# Grove-EMG_Sensor_v1_0.net
KiCad netlist of a schematic drawn in EAGLE
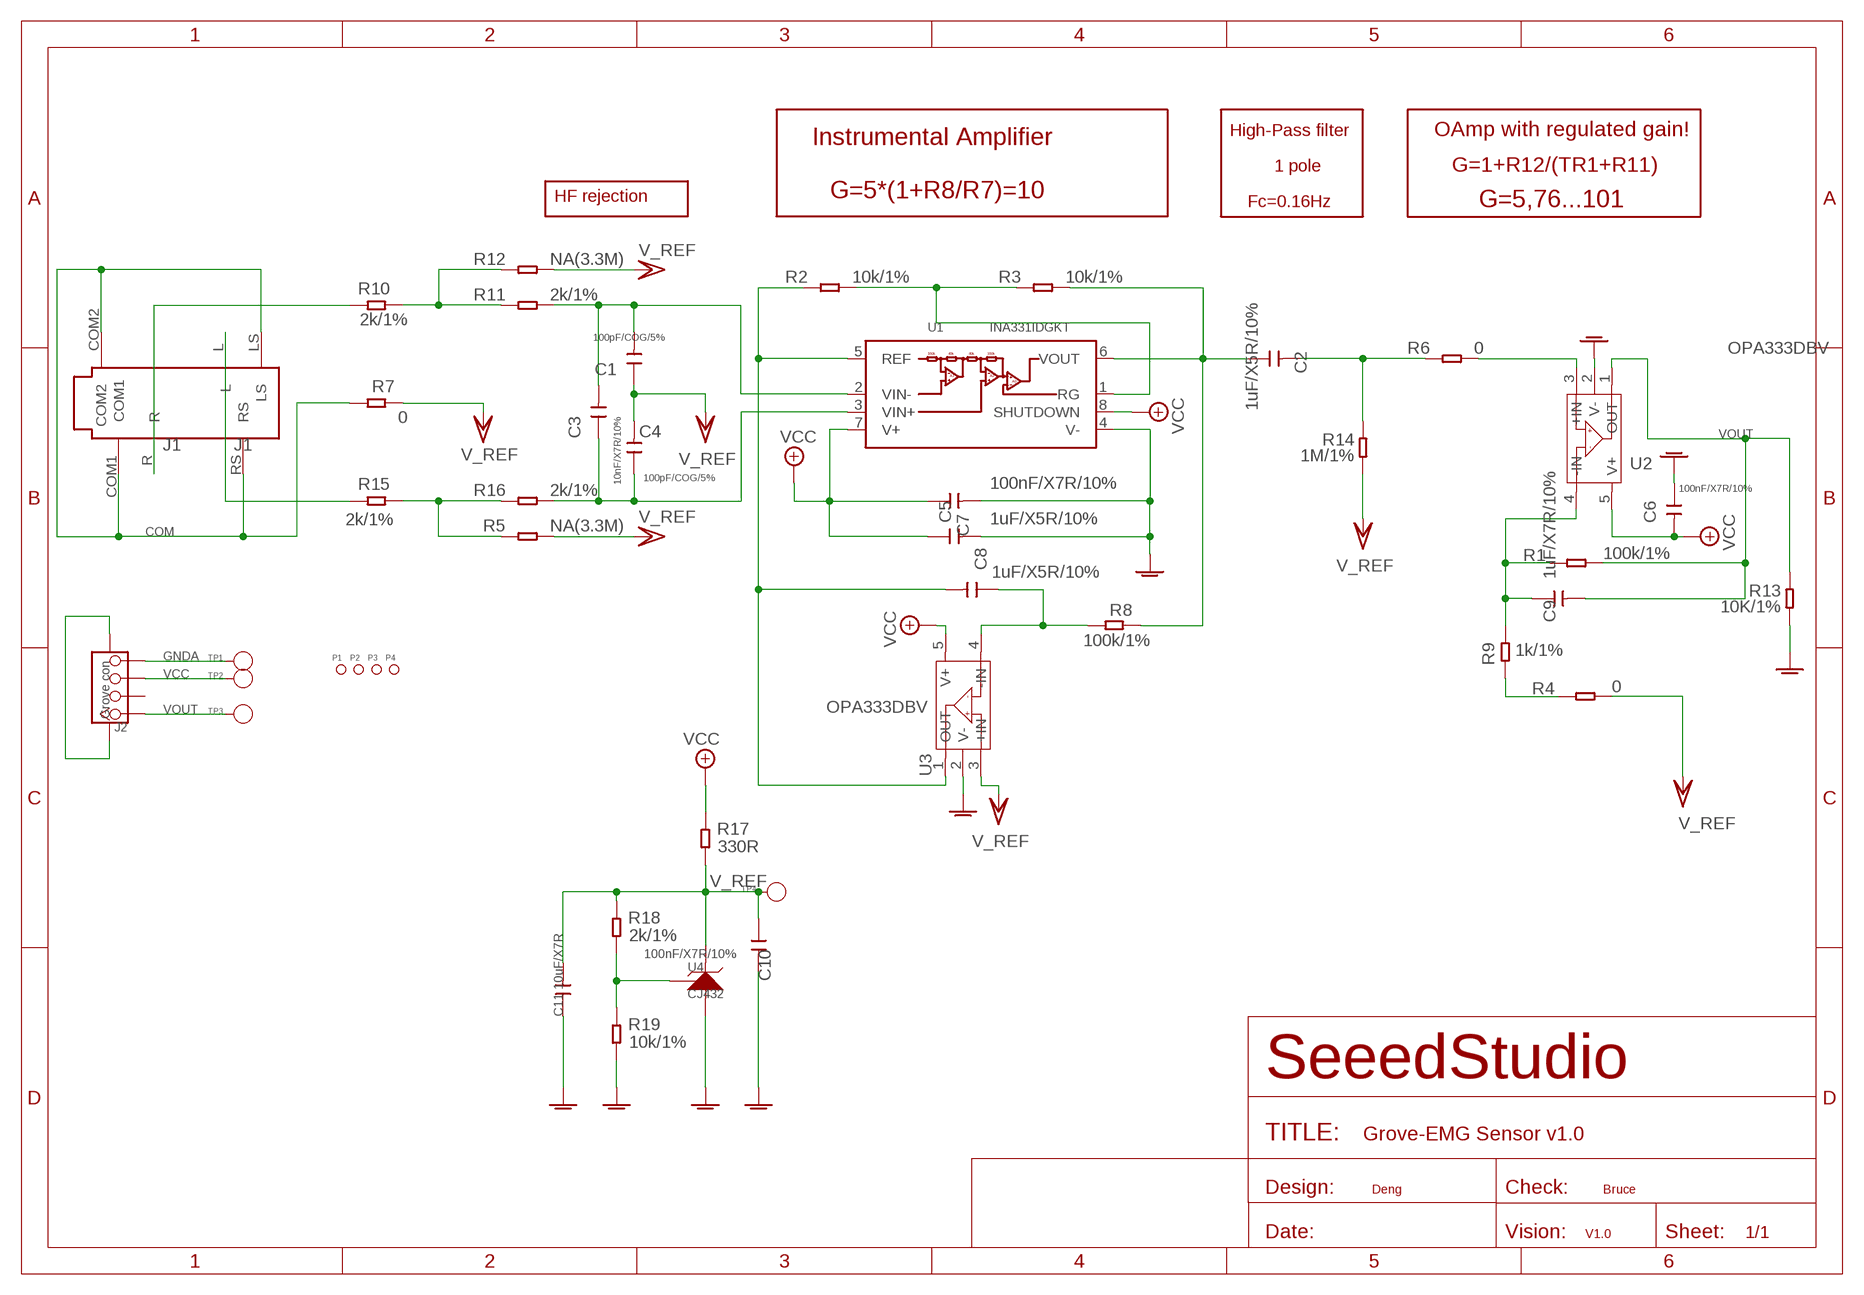
[diagram p0: schematic, sheet 1]

(export (version "E")
  (design (tool "Eeschema 10.0.6"))
  (components
    (comp (ref "C1")
      (value "100pF/COG/5%")
      (footprint "eagle-import:C0603")
      (libsource (lib "eagle-import") (part "C-0603"))
    )
    (comp (ref "C2")
      (value "1uF/X5R/10%")
      (footprint "eagle-import:C0603")
      (libsource (lib "eagle-import") (part "C-0603"))
    )
    (comp (ref "C3")
      (value "10nF/X7R/10%")
      (footprint "eagle-import:C0603")
      (libsource (lib "eagle-import") (part "C-0603"))
    )
    (comp (ref "C4")
      (value "100pF/COG/5%")
      (footprint "eagle-import:C0603")
      (libsource (lib "eagle-import") (part "C-0603"))
    )
    (comp (ref "C5")
      (value "100nF/X7R/10%")
      (footprint "eagle-import:C0603")
      (libsource (lib "eagle-import") (part "C-0603"))
    )
    (comp (ref "C6")
      (value "100nF/X7R/10%")
      (footprint "eagle-import:C0603")
      (libsource (lib "eagle-import") (part "C-0603"))
    )
    (comp (ref "C7")
      (value "1uF/X5R/10%")
      (footprint "eagle-import:C0603")
      (libsource (lib "eagle-import") (part "C-0603"))
    )
    (comp (ref "C8")
      (value "1uF/X5R/10%")
      (footprint "eagle-import:C0603")
      (libsource (lib "eagle-import") (part "C-0603"))
    )
    (comp (ref "C9")
      (value "1uF/X7R/10%")
      (footprint "eagle-import:C0603")
      (libsource (lib "eagle-import") (part "C-0603"))
    )
    (comp (ref "C10")
      (value "100nF/X7R/10%")
      (footprint "eagle-import:C0603")
      (libsource (lib "eagle-import") (part "C-0603"))
    )
    (comp (ref "C11")
      (value "10uF/X7R")
      (footprint "eagle-import:C0805")
      (libsource (lib "eagle-import") (part "C-0805"))
    )
    (comp (ref "J1")
      (value "J1")
      (footprint "eagle-import:6P-SMD-3.5-NEW")
      (libsource (lib "eagle-import") (part "AUDIO-6P-SMD"))
    )
    (comp (ref "J2")
      (value "Grove con")
      (footprint "eagle-import:4P-SMD-2.0")
      (libsource (lib "eagle-import") (part "TWIG-4P-2.0-SMD-FEMALE-REINFORCE'DD'"))
    )
    (comp (ref "P1")
      (value "PAD-MARK")
      (footprint "eagle-import:ROUND-MARK-1.0")
      (fields (field (name "PARTNO") "DNP"))
      (libsource (lib "eagle-import") (part "PAD-MARK"))
    )
    (comp (ref "P2")
      (value "PAD-MARK")
      (footprint "eagle-import:ROUND-MARK-1.0")
      (fields (field (name "PARTNO") "DNP"))
      (libsource (lib "eagle-import") (part "PAD-MARK"))
    )
    (comp (ref "P3")
      (value "PAD-MARK")
      (footprint "eagle-import:ROUND-MARK-1.0")
      (fields (field (name "PARTNO") "DNP"))
      (libsource (lib "eagle-import") (part "PAD-MARK"))
    )
    (comp (ref "P4")
      (value "PAD-MARK")
      (footprint "eagle-import:ROUND-MARK-1.0")
      (fields (field (name "PARTNO") "DNP"))
      (libsource (lib "eagle-import") (part "PAD-MARK"))
    )
    (comp (ref "R1")
      (value "100k/1%")
      (footprint "eagle-import:R0603")
      (libsource (lib "eagle-import") (part "R-0603"))
    )
    (comp (ref "R2")
      (value "10k/1%")
      (footprint "eagle-import:R0603")
      (libsource (lib "eagle-import") (part "R-0603"))
    )
    (comp (ref "R3")
      (value "10k/1%")
      (footprint "eagle-import:R0603")
      (libsource (lib "eagle-import") (part "R-0603"))
    )
    (comp (ref "R4")
      (value "0")
      (footprint "eagle-import:R0603")
      (libsource (lib "eagle-import") (part "R-0603"))
    )
    (comp (ref "R5")
      (value "NA(3.3M)")
      (footprint "eagle-import:R0603")
      (libsource (lib "eagle-import") (part "R-0603"))
    )
    (comp (ref "R6")
      (value "0")
      (footprint "eagle-import:R0603")
      (libsource (lib "eagle-import") (part "R-0603"))
    )
    (comp (ref "R7")
      (value "0")
      (footprint "eagle-import:R0603")
      (libsource (lib "eagle-import") (part "R-0603"))
    )
    (comp (ref "R8")
      (value "100k/1%")
      (footprint "eagle-import:R0603")
      (libsource (lib "eagle-import") (part "R-0603"))
    )
    (comp (ref "R9")
      (value "1k/1%")
      (footprint "eagle-import:R0603")
      (libsource (lib "eagle-import") (part "R-0603"))
    )
    (comp (ref "R10")
      (value "2k/1%")
      (footprint "eagle-import:R0603")
      (libsource (lib "eagle-import") (part "R-0603"))
    )
    (comp (ref "R11")
      (value "2k/1%")
      (footprint "eagle-import:R0603")
      (libsource (lib "eagle-import") (part "R-0603"))
    )
    (comp (ref "R12")
      (value "NA(3.3M)")
      (footprint "eagle-import:R0603")
      (libsource (lib "eagle-import") (part "R-0603"))
    )
    (comp (ref "R13")
      (value "10K/1%")
      (footprint "eagle-import:R0603")
      (libsource (lib "eagle-import") (part "R-0603"))
    )
    (comp (ref "R14")
      (value "1M/1%")
      (footprint "eagle-import:R0603")
      (libsource (lib "eagle-import") (part "R-0603"))
    )
    (comp (ref "R15")
      (value "2k/1%")
      (footprint "eagle-import:R0603")
      (libsource (lib "eagle-import") (part "R-0603"))
    )
    (comp (ref "R16")
      (value "2k/1%")
      (footprint "eagle-import:R0603")
      (libsource (lib "eagle-import") (part "R-0603"))
    )
    (comp (ref "R17")
      (value "330R")
      (footprint "eagle-import:R0603")
      (libsource (lib "eagle-import") (part "R-0603"))
    )
    (comp (ref "R18")
      (value "2k/1%")
      (footprint "eagle-import:R0603")
      (libsource (lib "eagle-import") (part "R-0603"))
    )
    (comp (ref "R19")
      (value "10k/1%")
      (footprint "eagle-import:R0603")
      (libsource (lib "eagle-import") (part "R-0603"))
    )
    (comp (ref "TP1")
      (value "TP1")
      (footprint "eagle-import:TP_4545")
      (fields (field (name "PARTNO") "DNP"))
      (libsource (lib "eagle-import") (part "PAD-TEST-POINT'4545'"))
    )
    (comp (ref "TP2")
      (value "TP2")
      (footprint "eagle-import:TP_4545")
      (fields (field (name "PARTNO") "DNP"))
      (libsource (lib "eagle-import") (part "PAD-TEST-POINT'4545'"))
    )
    (comp (ref "TP3")
      (value "TP3")
      (footprint "eagle-import:TP_4545")
      (fields (field (name "PARTNO") "DNP"))
      (libsource (lib "eagle-import") (part "PAD-TEST-POINT'4545'"))
    )
    (comp (ref "TP4")
      (value "TP4")
      (footprint "eagle-import:TP_4545")
      (fields (field (name "PARTNO") "DNP"))
      (libsource (lib "eagle-import") (part "PAD-TEST-POINT'4545'"))
    )
    (comp (ref "U1")
      (value "INA331IDGKT")
      (footprint "eagle-import:MSOP-8")
      (libsource (lib "eagle-import") (part "INA331EA"))
    )
    (comp (ref "U2")
      (value "OPA333DBV")
      (footprint "eagle-import:SOT23-5")
      (libsource (lib "eagle-import") (part "OPA333DBV"))
    )
    (comp (ref "U3")
      (value "OPA333DBV")
      (footprint "eagle-import:SOT23-5")
      (libsource (lib "eagle-import") (part "OPA333DBV"))
    )
    (comp (ref "U4")
      (value "CJ432")
      (footprint "eagle-import:SOT23")
      (libsource (lib "eagle-import") (part "REFERENCE-SOURCE"))
    )
  )
  (nets
    (net (code "1") (name "/COM") (class "Default")
      (node (ref "J1") (pin "COM1") (pinfunction "COM1_COM1") (pintype "bidirectional"))
      (node (ref "J1") (pin "COM2") (pinfunction "COM2_COM2") (pintype "bidirectional"))
      (node (ref "J1") (pin "LS") (pinfunction "LS_LS") (pintype "bidirectional"))
      (node (ref "J1") (pin "RS") (pinfunction "RS_RS") (pintype "bidirectional"))
      (node (ref "R7") (pin "1") (pinfunction "1_1") (pintype "passive"))
    )
    (net (code "2") (name "/VOUT") (class "Default")
      (node (ref "C9") (pin "2") (pinfunction "2_2") (pintype "passive"))
      (node (ref "J2") (pin "1") (pinfunction "1_1") (pintype "bidirectional"))
      (node (ref "R1") (pin "2") (pinfunction "2_2") (pintype "passive"))
      (node (ref "R13") (pin "1") (pinfunction "1_1") (pintype "passive"))
      (node (ref "TP3") (pin "T") (pinfunction "T_T") (pintype "bidirectional"))
      (node (ref "U2") (pin "1") (pinfunction "OUT_1") (pintype "bidirectional"))
    )
    (net (code "3") (name "GNDA") (class "Default")
      (node (ref "C10") (pin "2") (pinfunction "2_2") (pintype "passive"))
      (node (ref "C11") (pin "1") (pinfunction "1_1") (pintype "passive"))
      (node (ref "C5") (pin "2") (pinfunction "2_2") (pintype "passive"))
      (node (ref "C6") (pin "1") (pinfunction "1_1") (pintype "passive"))
      (node (ref "C7") (pin "2") (pinfunction "2_2") (pintype "passive"))
      (node (ref "J2") (pin "4") (pinfunction "4_4") (pintype "bidirectional"))
      (node (ref "R13") (pin "2") (pinfunction "2_2") (pintype "passive"))
      (node (ref "R19") (pin "1") (pinfunction "1_1") (pintype "passive"))
      (node (ref "TP1") (pin "T") (pinfunction "T_T") (pintype "bidirectional"))
      (node (ref "U1") (pin "4") (pinfunction "V-_4") (pintype "power_in"))
      (node (ref "U2") (pin "2") (pinfunction "V-_2") (pintype "bidirectional"))
      (node (ref "U3") (pin "2") (pinfunction "V-_2") (pintype "bidirectional"))
      (node (ref "U4") (pin "3") (pinfunction "A_3") (pintype "bidirectional"))
    )
    (net (code "4") (name "Net-(C2-Pad2)") (class "Default")
      (node (ref "C2") (pin "2") (pinfunction "2_2") (pintype "passive"))
      (node (ref "R14") (pin "1") (pinfunction "1_1") (pintype "passive"))
      (node (ref "R6") (pin "2") (pinfunction "2_2") (pintype "passive"))
    )
    (net (code "5") (name "Net-(J1-PadL)") (class "Default")
      (node (ref "J1") (pin "L") (pinfunction "L_L") (pintype "bidirectional"))
      (node (ref "R15") (pin "1") (pinfunction "1_1") (pintype "passive"))
    )
    (net (code "6") (name "Net-(J1-PadR)") (class "Default")
      (node (ref "J1") (pin "R") (pinfunction "R_R") (pintype "bidirectional"))
      (node (ref "R10") (pin "1") (pinfunction "1_1") (pintype "passive"))
    )
    (net (code "7") (name "Net-(R4-Pad1)") (class "Default")
      (node (ref "R4") (pin "1") (pinfunction "1_1") (pintype "passive"))
      (node (ref "R9") (pin "2") (pinfunction "2_2") (pintype "passive"))
    )
    (net (code "8") (name "Net-(R10-Pad2)") (class "Default")
      (node (ref "R10") (pin "2") (pinfunction "2_2") (pintype "passive"))
      (node (ref "R11") (pin "2") (pinfunction "2_2") (pintype "passive"))
      (node (ref "R12") (pin "2") (pinfunction "2_2") (pintype "passive"))
    )
    (net (code "9") (name "Net-(R15-Pad2)") (class "Default")
      (node (ref "R15") (pin "2") (pinfunction "2_2") (pintype "passive"))
      (node (ref "R16") (pin "2") (pinfunction "2_2") (pintype "passive"))
      (node (ref "R5") (pin "2") (pinfunction "2_2") (pintype "passive"))
    )
    (net (code "10") (name "Net-(U1-REF)") (class "Default")
      (node (ref "C8") (pin "2") (pinfunction "2_2") (pintype "passive"))
      (node (ref "R2") (pin "2") (pinfunction "2_2") (pintype "passive"))
      (node (ref "U1") (pin "5") (pinfunction "REF_5") (pintype "input"))
      (node (ref "U3") (pin "1") (pinfunction "OUT_1") (pintype "bidirectional"))
    )
    (net (code "11") (name "Net-(U1-RG)") (class "Default")
      (node (ref "R2") (pin "1") (pinfunction "1_1") (pintype "passive"))
      (node (ref "R3") (pin "2") (pinfunction "2_2") (pintype "passive"))
      (node (ref "U1") (pin "1") (pinfunction "RG_1") (pintype "input"))
    )
    (net (code "12") (name "Net-(U1-VIN+)") (class "Default")
      (node (ref "C3") (pin "1") (pinfunction "1_1") (pintype "passive"))
      (node (ref "C4") (pin "1") (pinfunction "1_1") (pintype "passive"))
      (node (ref "R16") (pin "1") (pinfunction "1_1") (pintype "passive"))
      (node (ref "U1") (pin "3") (pinfunction "VIN+_3") (pintype "input"))
    )
    (net (code "13") (name "Net-(U1-VIN-)") (class "Default")
      (node (ref "C1") (pin "2") (pinfunction "2_2") (pintype "passive"))
      (node (ref "C3") (pin "2") (pinfunction "2_2") (pintype "passive"))
      (node (ref "R11") (pin "1") (pinfunction "1_1") (pintype "passive"))
      (node (ref "U1") (pin "2") (pinfunction "VIN-_2") (pintype "input"))
    )
    (net (code "14") (name "Net-(U1-VOUT)") (class "Default")
      (node (ref "C2") (pin "1") (pinfunction "1_1") (pintype "passive"))
      (node (ref "R3") (pin "1") (pinfunction "1_1") (pintype "passive"))
      (node (ref "R8") (pin "2") (pinfunction "2_2") (pintype "passive"))
      (node (ref "U1") (pin "6") (pinfunction "VOUT_6") (pintype "output"))
    )
    (net (code "15") (name "Net-(U2-+IN)") (class "Default")
      (node (ref "R6") (pin "1") (pinfunction "1_1") (pintype "passive"))
      (node (ref "U2") (pin "3") (pinfunction "+IN_3") (pintype "bidirectional"))
    )
    (net (code "16") (name "Net-(U2--IN)") (class "Default")
      (node (ref "C9") (pin "1") (pinfunction "1_1") (pintype "passive"))
      (node (ref "R1") (pin "1") (pinfunction "1_1") (pintype "passive"))
      (node (ref "R9") (pin "1") (pinfunction "1_1") (pintype "passive"))
      (node (ref "U2") (pin "4") (pinfunction "-IN_4") (pintype "bidirectional"))
    )
    (net (code "17") (name "Net-(U3--IN)") (class "Default")
      (node (ref "C8") (pin "1") (pinfunction "1_1") (pintype "passive"))
      (node (ref "R8") (pin "1") (pinfunction "1_1") (pintype "passive"))
      (node (ref "U3") (pin "4") (pinfunction "-IN_4") (pintype "bidirectional"))
    )
    (net (code "18") (name "Net-(U4-R)") (class "Default")
      (node (ref "R18") (pin "1") (pinfunction "1_1") (pintype "passive"))
      (node (ref "R19") (pin "2") (pinfunction "2_2") (pintype "passive"))
      (node (ref "U4") (pin "1") (pinfunction "R_1") (pintype "bidirectional"))
    )
    (net (code "19") (name "VCC") (class "Default")
      (node (ref "C5") (pin "1") (pinfunction "1_1") (pintype "passive"))
      (node (ref "C6") (pin "2") (pinfunction "2_2") (pintype "passive"))
      (node (ref "C7") (pin "1") (pinfunction "1_1") (pintype "passive"))
      (node (ref "J2") (pin "3") (pinfunction "3_3") (pintype "bidirectional"))
      (node (ref "R17") (pin "2") (pinfunction "2_2") (pintype "passive"))
      (node (ref "TP2") (pin "T") (pinfunction "T_T") (pintype "bidirectional"))
      (node (ref "U1") (pin "7") (pinfunction "V+_7") (pintype "power_in"))
      (node (ref "U1") (pin "8") (pinfunction "SHUTDOWN_8") (pintype "input"))
      (node (ref "U2") (pin "5") (pinfunction "V+_5") (pintype "bidirectional"))
      (node (ref "U3") (pin "5") (pinfunction "V+_5") (pintype "bidirectional"))
    )
    (net (code "20") (name "V_REF") (class "Default")
      (node (ref "C1") (pin "1") (pinfunction "1_1") (pintype "passive"))
      (node (ref "C10") (pin "1") (pinfunction "1_1") (pintype "passive"))
      (node (ref "C11") (pin "2") (pinfunction "2_2") (pintype "passive"))
      (node (ref "C4") (pin "2") (pinfunction "2_2") (pintype "passive"))
      (node (ref "J2") (pin "SS1") (pinfunction "SS1_SS1") (pintype "bidirectional"))
      (node (ref "J2") (pin "SS2") (pinfunction "SS2_SS2") (pintype "bidirectional"))
      (node (ref "R12") (pin "1") (pinfunction "1_1") (pintype "passive"))
      (node (ref "R14") (pin "2") (pinfunction "2_2") (pintype "passive"))
      (node (ref "R17") (pin "1") (pinfunction "1_1") (pintype "passive"))
      (node (ref "R18") (pin "2") (pinfunction "2_2") (pintype "passive"))
      (node (ref "R4") (pin "2") (pinfunction "2_2") (pintype "passive"))
      (node (ref "R5") (pin "1") (pinfunction "1_1") (pintype "passive"))
      (node (ref "R7") (pin "2") (pinfunction "2_2") (pintype "passive"))
      (node (ref "TP4") (pin "T") (pinfunction "T_T") (pintype "bidirectional"))
      (node (ref "U3") (pin "3") (pinfunction "+IN_3") (pintype "bidirectional"))
      (node (ref "U4") (pin "2") (pinfunction "K_2") (pintype "bidirectional"))
    )
    (net (code "21") (name "unconnected-(J2-Pad2)") (class "Default")
      (node (ref "J2") (pin "2") (pinfunction "2_2") (pintype "bidirectional"))
    )
  )
)
